# ISO_I2C.net
KiCad netlist of a schematic drawn in Altium Designer
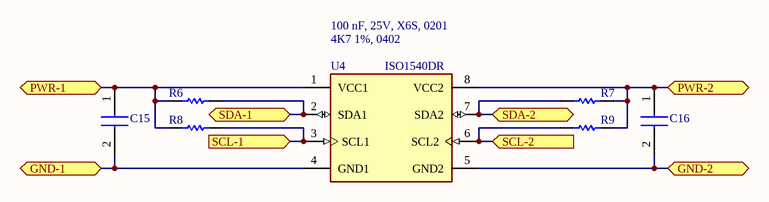
[diagram p0: ISO_I2C.SchDoc]

(export (version "E")
  (design (tool "Eeschema 10.0.6"))
  (components
    (comp (ref "C15")
      (value "100 nF, 25V, X6S, 0201")
      (footprint "SamacSys:CAPC0603X33N")
      (description "Capacitor")
      (fields
        (field (name "MANUFACTURER_PART_NUMBER") "GRM033C81E104KE14D")
        (field (name "MOUSER PART NUMBER") "81-GRM33C81E104KE14D")
      )
      (libsource (lib "*") (part "GRM033C81E104KE14D"))
    )
    (comp (ref "C16")
      (value "100 nF, 25V, X6S, 0201")
      (footprint "SamacSys:CAPC0603X33N")
      (description "Capacitor")
      (fields
        (field (name "MANUFACTURER_PART_NUMBER") "GRM033C81E104KE14D")
        (field (name "MOUSER PART NUMBER") "81-GRM33C81E104KE14D")
      )
      (libsource (lib "*") (part "GRM033C81E104KE14D"))
    )
    (comp (ref "R6")
      (value "4K7 1%, 0402")
      (footprint "RESC1005X40X25LL05T05")
      (description "Chip Resistor, 4.7 KOhm, +/- 1%, 0.1 W, -55 to 155 degC, 0402 (1005 Metric), RoHS, Tape and Reel")
      (fields (field (name "TOLERANCE") "1%") (field (name "PARTNUMBER") "ERJ-2RKF4701X"))
      (libsource (lib "Altium Content Vault") (part "RES-2"))
    )
    (comp (ref "R7")
      (value "4K7 1%, 0402")
      (footprint "RESC1005X40X25LL05T05")
      (description "Chip Resistor, 4.7 KOhm, +/- 1%, 0.1 W, -55 to 155 degC, 0402 (1005 Metric), RoHS, Tape and Reel")
      (fields (field (name "TOLERANCE") "1%") (field (name "PARTNUMBER") "ERJ-2RKF4701X"))
      (libsource (lib "Altium Content Vault") (part "RES-2"))
    )
    (comp (ref "R8")
      (value "4K7 1%, 0402")
      (footprint "RESC1005X40X25LL05T05")
      (description "Chip Resistor, 4.7 KOhm, +/- 1%, 0.1 W, -55 to 155 degC, 0402 (1005 Metric), RoHS, Tape and Reel")
      (fields (field (name "TOLERANCE") "1%") (field (name "PARTNUMBER") "ERJ-2RKF4701X"))
      (libsource (lib "Altium Content Vault") (part "RES-2"))
    )
    (comp (ref "R9")
      (value "4K7 1%, 0402")
      (footprint "RESC1005X40X25LL05T05")
      (description "Chip Resistor, 4.7 KOhm, +/- 1%, 0.1 W, -55 to 155 degC, 0402 (1005 Metric), RoHS, Tape and Reel")
      (fields (field (name "TOLERANCE") "1%") (field (name "PARTNUMBER") "ERJ-2RKF4701X"))
      (libsource (lib "Altium Content Vault") (part "RES-2"))
    )
    (comp (ref "U4")
      (value "ISO1540DR")
      (footprint "FP-D0008A-MFG")
      (description "DGTL ISO 2.5KV 2CH I2C 8SOIC")
      (fields
        (field (name "OCTOPART") "https://octopart.com/iso1540dr-texas+instruments-24334113")
        (field (name "MANUFACTURER") "Texas Instruments")
      )
      (libsource (lib "Altium Content Vault") (part "d824faccee5d143ad01692c0ddd1d85"))
    )
  )
  (nets
    (net (code "1") (name "/GND-1") (class "Default")
      (node (ref "C15") (pin "2") (pinfunction "2_2") (pintype "passive"))
      (node (ref "U4") (pin "4") (pinfunction "GND1_4") (pintype "power_in"))
    )
    (net (code "2") (name "/GND-2") (class "Default")
      (node (ref "C16") (pin "2") (pinfunction "2_2") (pintype "passive"))
      (node (ref "U4") (pin "5") (pinfunction "GND2_5") (pintype "power_in"))
    )
    (net (code "3") (name "/PWR-1") (class "Default")
      (node (ref "C15") (pin "1") (pinfunction "1_1") (pintype "passive"))
      (node (ref "R6") (pin "2") (pinfunction "2_2") (pintype "passive"))
      (node (ref "R8") (pin "2") (pinfunction "2_2") (pintype "passive"))
      (node (ref "U4") (pin "1") (pinfunction "VCC1_1") (pintype "power_in"))
    )
    (net (code "4") (name "/PWR-2") (class "Default")
      (node (ref "C16") (pin "1") (pinfunction "1_1") (pintype "passive"))
      (node (ref "R7") (pin "1") (pinfunction "1_1") (pintype "passive"))
      (node (ref "R9") (pin "1") (pinfunction "1_1") (pintype "passive"))
      (node (ref "U4") (pin "8") (pinfunction "VCC2_8") (pintype "power_in"))
    )
    (net (code "5") (name "/SCL-1") (class "Default")
      (node (ref "R8") (pin "1") (pinfunction "1_1") (pintype "passive"))
      (node (ref "U4") (pin "3") (pinfunction "SCL1_3") (pintype "input"))
    )
    (net (code "6") (name "/SCL-2") (class "Default")
      (node (ref "R9") (pin "2") (pinfunction "2_2") (pintype "passive"))
      (node (ref "U4") (pin "6") (pinfunction "SCL2_6") (pintype "input"))
    )
    (net (code "7") (name "/SDA-1") (class "Default")
      (node (ref "R6") (pin "1") (pinfunction "1_1") (pintype "passive"))
      (node (ref "U4") (pin "2") (pinfunction "SDA1_2") (pintype "bidirectional"))
    )
    (net (code "8") (name "/SDA-2") (class "Default")
      (node (ref "R7") (pin "2") (pinfunction "2_2") (pintype "passive"))
      (node (ref "U4") (pin "7") (pinfunction "SDA2_7") (pintype "bidirectional"))
    )
  )
)
